# 24_063_24_069.net
KiCad netlist of a schematic drawn in Altium Designer
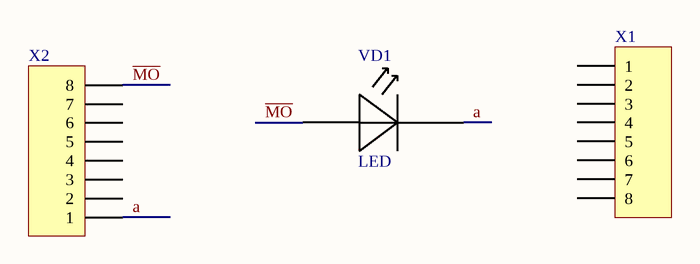
[diagram p0: 24.063_24.069.SchDoc]

(export (version "E")
  (design (tool "Eeschema 10.0.6"))
  (components
    (comp (ref "VD1") (value "LED") (footprint "LED 24.063") (libsource (lib "msp_SchLib") (part "LED")))
    (comp (ref "X1")
      (value "Header 8")
      (footprint "HDR1X8")
      (description "Header, 8-Pin")
      (fields (field (name "PUBLISHER") "Altium Limited"))
      (libsource (lib "Miscellaneous Connectors") (part "Header 8"))
    )
    (comp (ref "X2")
      (value "Header 8")
      (footprint "HDR1X8")
      (description "Header, 8-Pin")
      (fields (field (name "PUBLISHER") "Altium Limited"))
      (libsource (lib "") (part "Header 8_1"))
    )
  )
  (nets
    (net (code "1") (name "/a") (class "Default")
      (node (ref "VD1") (pin "2") (pinfunction "2_2") (pintype "passive"))
      (node (ref "X2") (pin "1") (pinfunction "1_1") (pintype "passive"))
    )
    (net (code "2") (name "/~{MO}") (class "Default")
      (node (ref "VD1") (pin "1") (pinfunction "1_1") (pintype "passive"))
      (node (ref "X2") (pin "8") (pinfunction "8_8") (pintype "passive"))
    )
    (net (code "3") (name "unconnected-(X1-Pad1)") (class "Default")
      (node (ref "X1") (pin "1") (pinfunction "1_1") (pintype "passive"))
    )
    (net (code "4") (name "unconnected-(X1-Pad2)") (class "Default")
      (node (ref "X1") (pin "2") (pinfunction "2_2") (pintype "passive"))
    )
    (net (code "5") (name "unconnected-(X1-Pad3)") (class "Default")
      (node (ref "X1") (pin "3") (pinfunction "3_3") (pintype "passive"))
    )
    (net (code "6") (name "unconnected-(X1-Pad4)") (class "Default")
      (node (ref "X1") (pin "4") (pinfunction "4_4") (pintype "passive"))
    )
    (net (code "7") (name "unconnected-(X1-Pad5)") (class "Default")
      (node (ref "X1") (pin "5") (pinfunction "5_5") (pintype "passive"))
    )
    (net (code "8") (name "unconnected-(X1-Pad6)") (class "Default")
      (node (ref "X1") (pin "6") (pinfunction "6_6") (pintype "passive"))
    )
    (net (code "9") (name "unconnected-(X1-Pad7)") (class "Default")
      (node (ref "X1") (pin "7") (pinfunction "7_7") (pintype "passive"))
    )
    (net (code "10") (name "unconnected-(X1-Pad8)") (class "Default")
      (node (ref "X1") (pin "8") (pinfunction "8_8") (pintype "passive"))
    )
    (net (code "11") (name "unconnected-(X2-Pad2)") (class "Default")
      (node (ref "X2") (pin "2") (pinfunction "2_2") (pintype "passive"))
    )
    (net (code "12") (name "unconnected-(X2-Pad3)") (class "Default")
      (node (ref "X2") (pin "3") (pinfunction "3_3") (pintype "passive"))
    )
    (net (code "13") (name "unconnected-(X2-Pad4)") (class "Default")
      (node (ref "X2") (pin "4") (pinfunction "4_4") (pintype "passive"))
    )
    (net (code "14") (name "unconnected-(X2-Pad5)") (class "Default")
      (node (ref "X2") (pin "5") (pinfunction "5_5") (pintype "passive"))
    )
    (net (code "15") (name "unconnected-(X2-Pad6)") (class "Default")
      (node (ref "X2") (pin "6") (pinfunction "6_6") (pintype "passive"))
    )
    (net (code "16") (name "unconnected-(X2-Pad7)") (class "Default")
      (node (ref "X2") (pin "7") (pinfunction "7_7") (pintype "passive"))
    )
  )
)
